# Sheet_1.net
KiCad netlist of a schematic drawn in Altium Designer
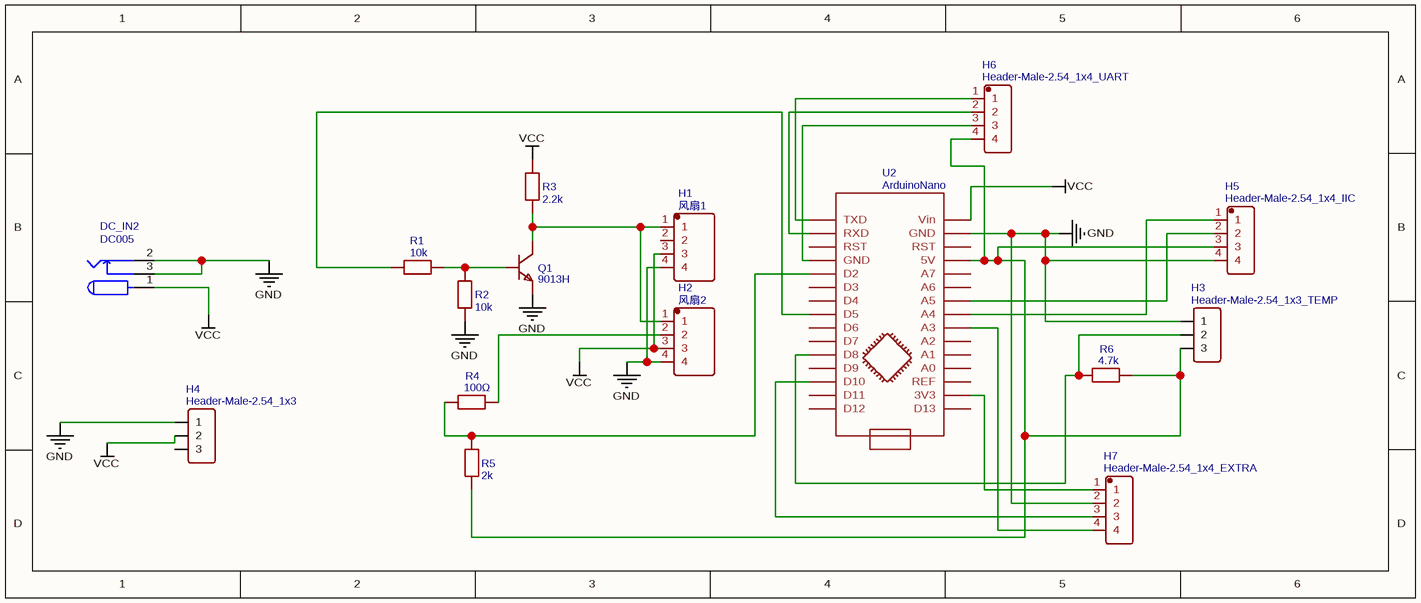
[diagram p0: Sheet_1.schdoc]

(export (version "E")
  (design (tool "Eeschema 10.0.6"))
  (components
    (comp (ref "DC_IN2")
      (value "DC005")
      (fields (field (name "CONTRIBUTOR") "nxnx"))
      (libsource (lib "altium-import") (part "root_0_DC005_"))
    )
    (comp (ref "H1")
      (value "风扇1")
      (fields
        (field (name "BOM_MANUFACTURER PART") "210S-1*4P L=11.6MMGold-plated black")
        (field (name "BOM_SUPPLIER PART") "C124378")
        (field (name "CONTRIBUTOR") "LCSC")
      )
      (libsource (lib "altium-import") (part "root_0_风扇1_"))
    )
    (comp (ref "H2")
      (value "风扇2")
      (fields
        (field (name "BOM_MANUFACTURER PART") "210S-1*4P L=11.6MMGold-plated black")
        (field (name "BOM_SUPPLIER PART") "C124378")
        (field (name "CONTRIBUTOR") "LCSC")
      )
      (libsource (lib "altium-import") (part "root_0_风扇2_"))
    )
    (comp (ref "H3")
      (value "Header-Male-2.54_1x3_TEMP")
      (fields
        (field (name "BOM_MANUFACTURER PART") "Header2.54mm 1*3P")
        (field (name "BOM_SUPPLIER PART") "C49257")
      )
      (libsource (lib "altium-import") (part "root_0_Header-Male-2.54_1x3_TEMP_"))
    )
    (comp (ref "H4")
      (value "Header-Male-2.54_1x3")
      (fields
        (field (name "BOM_MANUFACTURER PART") "Header2.54mm 1*3P")
        (field (name "BOM_SUPPLIER PART") "C49257")
      )
      (libsource (lib "altium-import") (part "root_0_Header-Male-2.54_1x3_"))
    )
    (comp (ref "H5")
      (value "Header-Male-2.54_1x4_IIC")
      (fields
        (field (name "BOM_MANUFACTURER PART") "Headers  Pins 1*4P")
        (field (name "BOM_SUPPLIER PART") "C59481")
      )
      (libsource (lib "altium-import") (part "root_0_Header-Male-2.54_1x4_IIC_"))
    )
    (comp (ref "H6")
      (value "Header-Male-2.54_1x4_UART")
      (fields
        (field (name "BOM_MANUFACTURER PART") "Headers  Pins 1*4P")
        (field (name "BOM_SUPPLIER PART") "C59481")
      )
      (libsource (lib "altium-import") (part "root_0_Header-Male-2.54_1x4_UART_"))
    )
    (comp (ref "H7")
      (value "Header-Male-2.54_1x4_EXTRA")
      (fields
        (field (name "BOM_MANUFACTURER PART") "Headers  Pins 1*4P")
        (field (name "BOM_SUPPLIER PART") "C59481")
      )
      (libsource (lib "altium-import") (part "root_0_Header-Male-2.54_1x4_EXTRA_"))
    )
    (comp (ref "Q1")
      (value "9013H")
      (fields (field (name "BOM_SUPPLIER PART") "C118553") (field (name "CONTRIBUTOR") "LCSC"))
      (libsource (lib "altium-import") (part "root_0_9013H_"))
    )
    (comp (ref "R1") (value "10k") (libsource (lib "altium-import") (part "root_0_10k_")))
    (comp (ref "R2") (value "10k") (libsource (lib "altium-import") (part "root_1_10k_")))
    (comp (ref "R3") (value "2.2k") (libsource (lib "altium-import") (part "root_1_2.2k_")))
    (comp (ref "R4") (value "100Ω") (libsource (lib "altium-import") (part "root_0_100Ω_")))
    (comp (ref "R5") (value "2k") (libsource (lib "altium-import") (part "root_1_2k_")))
    (comp (ref "R6") (value "4.7k") (libsource (lib "altium-import") (part "root_0_4.7k_")))
    (comp (ref "U2")
      (value "ArduinoNano")
      (fields (field (name "CONTRIBUTOR") "vincint810923"))
      (libsource (lib "altium-import") (part "root_0_ArduinoNano_"))
    )
  )
  (nets
    (net (code "1") (name "GND") (class "Default")
      (node (ref "DC_IN2") (pin "2") (pintype "passive"))
      (node (ref "DC_IN2") (pin "3") (pintype "passive"))
      (node (ref "H1") (pin "4") (pinfunction "4_4") (pintype "passive"))
      (node (ref "H2") (pin "4") (pinfunction "4_4") (pintype "passive"))
      (node (ref "H3") (pin "1") (pinfunction "1_1") (pintype "passive"))
      (node (ref "H4") (pin "1") (pinfunction "1_1") (pintype "passive"))
      (node (ref "H5") (pin "4") (pinfunction "4_4") (pintype "passive"))
      (node (ref "H7") (pin "2") (pinfunction "2_2") (pintype "passive"))
      (node (ref "Q1") (pin "1") (pinfunction "E_1") (pintype "passive"))
      (node (ref "R2") (pin "1") (pinfunction "1_1") (pintype "passive"))
      (node (ref "U2") (pin "29") (pinfunction "GND_29") (pintype "passive"))
    )
    (net (code "2") (name "Net-(H2-Pad2)") (class "Default")
      (node (ref "H2") (pin "2") (pinfunction "2_2") (pintype "passive"))
      (node (ref "R4") (pin "2") (pinfunction "2_2") (pintype "passive"))
    )
    (net (code "3") (name "Net-(H6-Pad3)") (class "Default")
      (node (ref "H6") (pin "3") (pinfunction "3_3") (pintype "passive"))
      (node (ref "U2") (pin "4") (pinfunction "GND_4") (pintype "passive"))
    )
    (net (code "4") (name "Net-(Q1-B)") (class "Default")
      (node (ref "Q1") (pin "2") (pinfunction "B_2") (pintype "passive"))
      (node (ref "R1") (pin "2") (pinfunction "2_2") (pintype "passive"))
      (node (ref "R2") (pin "2") (pinfunction "2_2") (pintype "passive"))
    )
    (net (code "5") (name "Net-(Q1-C)") (class "Default")
      (node (ref "H1") (pin "1") (pinfunction "1_1") (pintype "passive"))
      (node (ref "H2") (pin "1") (pinfunction "1_1") (pintype "passive"))
      (node (ref "Q1") (pin "3") (pinfunction "C_3") (pintype "passive"))
      (node (ref "R3") (pin "1") (pinfunction "1_1") (pintype "passive"))
    )
    (net (code "6") (name "Net-(U2-3V3)") (class "Default")
      (node (ref "H7") (pin "1") (pinfunction "1_1") (pintype "passive"))
      (node (ref "U2") (pin "17") (pinfunction "3V3_17") (pintype "passive"))
    )
    (net (code "7") (name "Net-(U2-5V)") (class "Default")
      (node (ref "H3") (pin "3") (pinfunction "3_3") (pintype "passive"))
      (node (ref "H5") (pin "3") (pinfunction "3_3") (pintype "passive"))
      (node (ref "H6") (pin "4") (pinfunction "4_4") (pintype "passive"))
      (node (ref "R5") (pin "1") (pinfunction "1_1") (pintype "passive"))
      (node (ref "R6") (pin "2") (pinfunction "2_2") (pintype "passive"))
      (node (ref "U2") (pin "27") (pinfunction "5V_27") (pintype "passive"))
    )
    (net (code "8") (name "Net-(U2-A3)") (class "Default")
      (node (ref "H7") (pin "4") (pinfunction "4_4") (pintype "passive"))
      (node (ref "U2") (pin "22") (pinfunction "A3_22") (pintype "passive"))
    )
    (net (code "9") (name "Net-(U2-A4)") (class "Default")
      (node (ref "H5") (pin "1") (pinfunction "1_1") (pintype "passive"))
      (node (ref "U2") (pin "23") (pinfunction "A4_23") (pintype "passive"))
    )
    (net (code "10") (name "Net-(U2-A5)") (class "Default")
      (node (ref "H5") (pin "2") (pinfunction "2_2") (pintype "passive"))
      (node (ref "U2") (pin "24") (pinfunction "A5_24") (pintype "passive"))
    )
    (net (code "11") (name "Net-(U2-D2)") (class "Default")
      (node (ref "R4") (pin "1") (pinfunction "1_1") (pintype "passive"))
      (node (ref "R5") (pin "2") (pinfunction "2_2") (pintype "passive"))
      (node (ref "U2") (pin "5") (pinfunction "D2_5") (pintype "passive"))
    )
    (net (code "12") (name "Net-(U2-D5)") (class "Default")
      (node (ref "R1") (pin "1") (pinfunction "1_1") (pintype "passive"))
      (node (ref "U2") (pin "8") (pinfunction "D5_8") (pintype "passive"))
    )
    (net (code "13") (name "Net-(U2-D8)") (class "Default")
      (node (ref "H3") (pin "2") (pinfunction "2_2") (pintype "passive"))
      (node (ref "R6") (pin "1") (pinfunction "1_1") (pintype "passive"))
      (node (ref "U2") (pin "11") (pinfunction "D8_11") (pintype "passive"))
    )
    (net (code "14") (name "Net-(U2-D10)") (class "Default")
      (node (ref "H7") (pin "3") (pinfunction "3_3") (pintype "passive"))
      (node (ref "U2") (pin "13") (pinfunction "D10_13") (pintype "passive"))
    )
    (net (code "15") (name "Net-(U2-RXD)") (class "Default")
      (node (ref "H6") (pin "2") (pinfunction "2_2") (pintype "passive"))
      (node (ref "U2") (pin "2") (pinfunction "RXD_2") (pintype "passive"))
    )
    (net (code "16") (name "Net-(U2-TXD)") (class "Default")
      (node (ref "H6") (pin "1") (pinfunction "1_1") (pintype "passive"))
      (node (ref "U2") (pin "1") (pinfunction "TXD_1") (pintype "passive"))
    )
    (net (code "17") (name "VCC") (class "Default")
      (node (ref "DC_IN2") (pin "1") (pintype "passive"))
      (node (ref "H1") (pin "3") (pinfunction "3_3") (pintype "passive"))
      (node (ref "H2") (pin "3") (pinfunction "3_3") (pintype "passive"))
      (node (ref "H4") (pin "2") (pinfunction "2_2") (pintype "passive"))
      (node (ref "R3") (pin "2") (pinfunction "2_2") (pintype "passive"))
      (node (ref "U2") (pin "30") (pinfunction "Vin_30") (pintype "passive"))
    )
    (net (code "18") (name "unconnected-(H1-Pad2)") (class "Default")
      (node (ref "H1") (pin "2") (pinfunction "2_2") (pintype "passive"))
    )
    (net (code "19") (name "unconnected-(H4-Pad3)") (class "Default")
      (node (ref "H4") (pin "3") (pinfunction "3_3") (pintype "passive"))
    )
    (net (code "20") (name "unconnected-(U2-A0-Pad19)") (class "Default")
      (node (ref "U2") (pin "19") (pinfunction "A0_19") (pintype "passive"))
    )
    (net (code "21") (name "unconnected-(U2-A1-Pad20)") (class "Default")
      (node (ref "U2") (pin "20") (pinfunction "A1_20") (pintype "passive"))
    )
    (net (code "22") (name "unconnected-(U2-A2-Pad21)") (class "Default")
      (node (ref "U2") (pin "21") (pinfunction "A2_21") (pintype "passive"))
    )
    (net (code "23") (name "unconnected-(U2-A6-Pad25)") (class "Default")
      (node (ref "U2") (pin "25") (pinfunction "A6_25") (pintype "passive"))
    )
    (net (code "24") (name "unconnected-(U2-A7-Pad26)") (class "Default")
      (node (ref "U2") (pin "26") (pinfunction "A7_26") (pintype "passive"))
    )
    (net (code "25") (name "unconnected-(U2-D3-Pad6)") (class "Default")
      (node (ref "U2") (pin "6") (pinfunction "D3_6") (pintype "passive"))
    )
    (net (code "26") (name "unconnected-(U2-D4-Pad7)") (class "Default")
      (node (ref "U2") (pin "7") (pinfunction "D4_7") (pintype "passive"))
    )
    (net (code "27") (name "unconnected-(U2-D6-Pad9)") (class "Default")
      (node (ref "U2") (pin "9") (pinfunction "D6_9") (pintype "passive"))
    )
    (net (code "28") (name "unconnected-(U2-D7-Pad10)") (class "Default")
      (node (ref "U2") (pin "10") (pinfunction "D7_10") (pintype "passive"))
    )
    (net (code "29") (name "unconnected-(U2-D9-Pad12)") (class "Default")
      (node (ref "U2") (pin "12") (pinfunction "D9_12") (pintype "passive"))
    )
    (net (code "30") (name "unconnected-(U2-D11-Pad14)") (class "Default")
      (node (ref "U2") (pin "14") (pinfunction "D11_14") (pintype "passive"))
    )
    (net (code "31") (name "unconnected-(U2-D12-Pad15)") (class "Default")
      (node (ref "U2") (pin "15") (pinfunction "D12_15") (pintype "passive"))
    )
    (net (code "32") (name "unconnected-(U2-D13-Pad16)") (class "Default")
      (node (ref "U2") (pin "16") (pinfunction "D13_16") (pintype "passive"))
    )
    (net (code "33") (name "unconnected-(U2-REF-Pad18)") (class "Default")
      (node (ref "U2") (pin "18") (pinfunction "REF_18") (pintype "passive"))
    )
    (net (code "34") (name "unconnected-(U2-RST-Pad3)") (class "Default")
      (node (ref "U2") (pin "3") (pinfunction "RST_3") (pintype "passive"))
    )
    (net (code "35") (name "unconnected-(U2-RST-Pad28)") (class "Default")
      (node (ref "U2") (pin "28") (pinfunction "RST_28") (pintype "passive"))
    )
  )
)
